# Switch_Board_Sch.net
KiCad netlist of a schematic drawn in Altium Designer
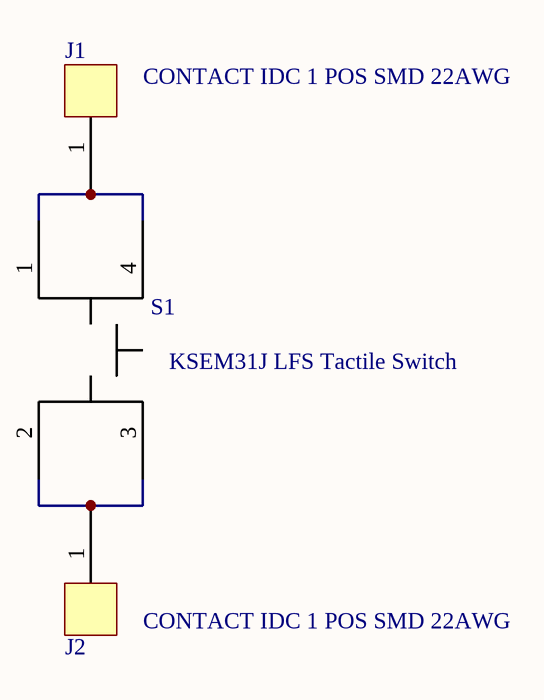
[diagram p0: Switch Board Sch.SchDoc]

(export (version "E")
  (design (tool "Eeschema 10.0.6"))
  (components
    (comp (ref "J1")
      (value "CONTACT IDC 1 POS SMD 22AWG")
      (footprint "CONTACT IDC 1 POS SMD 22AWG")
      (libsource (lib "") (part "CONTACT IDC 1 POS SMD 22AWG_1"))
    )
    (comp (ref "J2")
      (value "CONTACT IDC 1 POS SMD 22AWG")
      (footprint "CONTACT IDC 1 POS SMD 22AWG")
      (libsource (lib "Switch Board Lib") (part "CONTACT IDC 1 POS SMD 22AWG"))
    )
    (comp (ref "S1")
      (value "KSEM31J LFS Tactile Switch")
      (footprint "KSEM31J LFS Tactile Switch")
      (libsource (lib "Switch Board Lib") (part "KSEM31J LFS Tactile Switch"))
    )
  )
  (nets
    (net (code "1") (name "Net-(J1-Pad1)") (class "Default")
      (node (ref "J1") (pin "1") (pinfunction "1_1") (pintype "passive"))
      (node (ref "S1") (pin "1") (pinfunction "A_1") (pintype "passive"))
      (node (ref "S1") (pin "4") (pinfunction "A_4") (pintype "passive"))
    )
    (net (code "2") (name "Net-(J2-Pad1)") (class "Default")
      (node (ref "J2") (pin "1") (pinfunction "1_1") (pintype "passive"))
      (node (ref "S1") (pin "2") (pinfunction "B_2") (pintype "passive"))
      (node (ref "S1") (pin "3") (pinfunction "B_3") (pintype "passive"))
    )
  )
)
